# rx_board.net
KiCad netlist of a schematic drawn in EAGLE
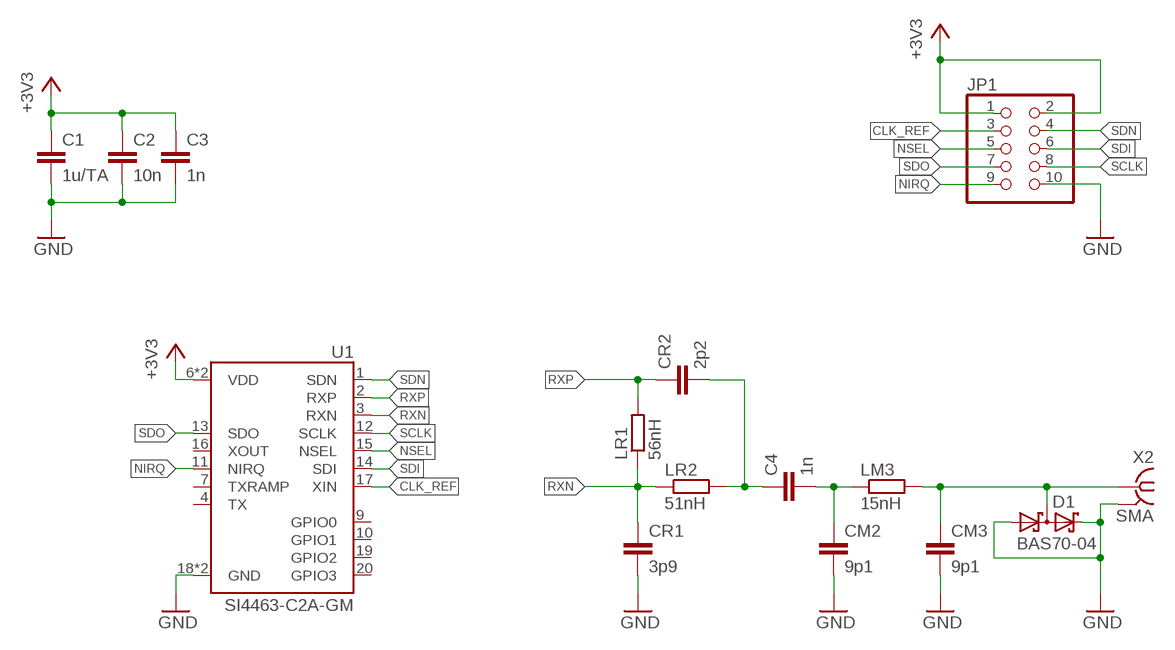
[diagram p0: schematic, sheet 1]

(export (version "E")
  (design (tool "Eeschema 10.0.6"))
  (components
    (comp (ref "C1")
      (value "1u/TA")
      (footprint "eagle-import:C1206")
      (libsource (lib "eagle-import") (part "C-EUC1206"))
    )
    (comp (ref "C2")
      (value "10n")
      (footprint "eagle-import:C0805")
      (libsource (lib "eagle-import") (part "C-EUC0805"))
    )
    (comp (ref "C3")
      (value "1n")
      (footprint "eagle-import:C0805")
      (libsource (lib "eagle-import") (part "C-EUC0805"))
    )
    (comp (ref "C4")
      (value "1n")
      (footprint "eagle-import:C0805")
      (libsource (lib "eagle-import") (part "C-EUC0805"))
    )
    (comp (ref "CM2")
      (value "9p1")
      (footprint "eagle-import:C0805")
      (libsource (lib "eagle-import") (part "C-EUC0805"))
    )
    (comp (ref "CM3")
      (value "9p1")
      (footprint "eagle-import:C0805")
      (libsource (lib "eagle-import") (part "C-EUC0805"))
    )
    (comp (ref "CR1")
      (value "3p9")
      (footprint "eagle-import:C0805")
      (libsource (lib "eagle-import") (part "C-EUC0805"))
    )
    (comp (ref "CR2")
      (value "2p2")
      (footprint "eagle-import:C0805")
      (libsource (lib "eagle-import") (part "C-EUC0805"))
    )
    (comp (ref "D1")
      (value "BAS70-04")
      (footprint "eagle-import:SOT23")
      (libsource (lib "eagle-import") (part "BAS70-04"))
    )
    (comp (ref "JP1")
      (value "PINHD-2X5/90")
      (footprint "eagle-import:2X05_90")
      (libsource (lib "eagle-import") (part "PINHD-2X5/90"))
    )
    (comp (ref "LM3")
      (value "15nH")
      (footprint "eagle-import:R0805")
      (libsource (lib "eagle-import") (part "R-EU_R0805"))
    )
    (comp (ref "LR1")
      (value "56nH")
      (footprint "eagle-import:R0805")
      (libsource (lib "eagle-import") (part "R-EU_R0805"))
    )
    (comp (ref "LR2")
      (value "51nH")
      (footprint "eagle-import:R0805")
      (libsource (lib "eagle-import") (part "R-EU_R0805"))
    )
    (comp (ref "U1")
      (value "SI4463-C2A-GM")
      (footprint "eagle-import:QFN50P400X400X90-20N")
      (fields (field (name "MF") "Silicon Labs"))
      (libsource (lib "eagle-import") (part "SI4463-C2A-GM"))
    )
    (comp (ref "X2")
      (value "SMA")
      (footprint "eagle-import:J502-ND-142-0701-871_876")
      (fields (field (name "MF") "JOHNSON COMPONENTS") (field (name "MPN") "142-0701-871"))
      (libsource (lib "eagle-import") (part "SMA-142-0701-871/876"))
    )
  )
  (nets
    (net (code "1") (name "+3V3") (class "Default")
      (node (ref "C1") (pin "1") (pinfunction "1_1") (pintype "passive"))
      (node (ref "C2") (pin "1") (pinfunction "1_1") (pintype "passive"))
      (node (ref "C3") (pin "1") (pinfunction "1_1") (pintype "passive"))
      (node (ref "JP1") (pin "1") (pinfunction "1_1") (pintype "passive"))
      (node (ref "JP1") (pin "2") (pinfunction "2_2") (pintype "passive"))
      (node (ref "U1") (pin "6") (pinfunction "VDD_6") (pintype "power_in"))
      (node (ref "U1") (pin "8") (pinfunction "VDD_8") (pintype "power_in"))
    )
    (net (code "2") (name "CLK_REF") (class "Default")
      (node (ref "JP1") (pin "3") (pinfunction "3_3") (pintype "passive"))
      (node (ref "U1") (pin "17") (pinfunction "XIN_17") (pintype "input"))
    )
    (net (code "3") (name "GND") (class "Default")
      (node (ref "C1") (pin "2") (pinfunction "2_2") (pintype "passive"))
      (node (ref "C2") (pin "2") (pinfunction "2_2") (pintype "passive"))
      (node (ref "C3") (pin "2") (pinfunction "2_2") (pintype "passive"))
      (node (ref "CM2") (pin "2") (pinfunction "2_2") (pintype "passive"))
      (node (ref "CM3") (pin "2") (pinfunction "2_2") (pintype "passive"))
      (node (ref "CR1") (pin "2") (pinfunction "2_2") (pintype "passive"))
      (node (ref "D1") (pin "1") (pinfunction "A1_1") (pintype "passive"))
      (node (ref "D1") (pin "2") (pinfunction "C2_2") (pintype "passive"))
      (node (ref "JP1") (pin "10") (pinfunction "10_10") (pintype "passive"))
      (node (ref "U1") (pin "18") (pinfunction "GND_18") (pintype "power_in"))
      (node (ref "U1") (pin "21") (pinfunction "GND_21") (pintype "power_in"))
      (node (ref "X2") (pin "G@1") (pinfunction "2_G@1") (pintype "passive"))
      (node (ref "X2") (pin "G@2") (pinfunction "2_G@2") (pintype "passive"))
      (node (ref "X2") (pin "G@3") (pinfunction "2_G@3") (pintype "passive"))
      (node (ref "X2") (pin "G@4") (pinfunction "2_G@4") (pintype "passive"))
    )
    (net (code "4") (name "NIRQ") (class "Default")
      (node (ref "JP1") (pin "9") (pinfunction "9_9") (pintype "passive"))
      (node (ref "U1") (pin "11") (pinfunction "NIRQ_11") (pintype "output"))
    )
    (net (code "5") (name "NSEL") (class "Default")
      (node (ref "JP1") (pin "5") (pinfunction "5_5") (pintype "passive"))
      (node (ref "U1") (pin "15") (pinfunction "NSEL_15") (pintype "input"))
    )
    (net (code "6") (name "Net-(C4-Pad1)") (class "Default")
      (node (ref "C4") (pin "1") (pinfunction "1_1") (pintype "passive"))
      (node (ref "CR2") (pin "2") (pinfunction "2_2") (pintype "passive"))
      (node (ref "LR2") (pin "2") (pinfunction "2_2") (pintype "passive"))
    )
    (net (code "7") (name "Net-(C4-Pad2)") (class "Default")
      (node (ref "C4") (pin "2") (pinfunction "2_2") (pintype "passive"))
      (node (ref "CM2") (pin "1") (pinfunction "1_1") (pintype "passive"))
      (node (ref "LM3") (pin "1") (pinfunction "1_1") (pintype "passive"))
    )
    (net (code "8") (name "Net-(D1-C1A2)") (class "Default")
      (node (ref "CM3") (pin "1") (pinfunction "1_1") (pintype "passive"))
      (node (ref "D1") (pin "3") (pinfunction "C1A2_3") (pintype "passive"))
      (node (ref "LM3") (pin "2") (pinfunction "2_2") (pintype "passive"))
      (node (ref "X2") (pin "1") (pinfunction "1_1") (pintype "passive"))
    )
    (net (code "9") (name "RXN") (class "Default")
      (node (ref "CR1") (pin "1") (pinfunction "1_1") (pintype "passive"))
      (node (ref "LR1") (pin "1") (pinfunction "1_1") (pintype "passive"))
      (node (ref "LR2") (pin "1") (pinfunction "1_1") (pintype "passive"))
      (node (ref "U1") (pin "3") (pinfunction "RXN_3") (pintype "input"))
    )
    (net (code "10") (name "RXP") (class "Default")
      (node (ref "CR2") (pin "1") (pinfunction "1_1") (pintype "passive"))
      (node (ref "LR1") (pin "2") (pinfunction "2_2") (pintype "passive"))
      (node (ref "U1") (pin "2") (pinfunction "RXP_2") (pintype "input"))
    )
    (net (code "11") (name "SCLK") (class "Default")
      (node (ref "JP1") (pin "8") (pinfunction "8_8") (pintype "passive"))
      (node (ref "U1") (pin "12") (pinfunction "SCLK_12") (pintype "input"))
    )
    (net (code "12") (name "SDI") (class "Default")
      (node (ref "JP1") (pin "6") (pinfunction "6_6") (pintype "passive"))
      (node (ref "U1") (pin "14") (pinfunction "SDI_14") (pintype "input"))
    )
    (net (code "13") (name "SDN") (class "Default")
      (node (ref "JP1") (pin "4") (pinfunction "4_4") (pintype "passive"))
      (node (ref "U1") (pin "1") (pinfunction "SDN_1") (pintype "input"))
    )
    (net (code "14") (name "SDO") (class "Default")
      (node (ref "JP1") (pin "7") (pinfunction "7_7") (pintype "passive"))
      (node (ref "U1") (pin "13") (pinfunction "SDO_13") (pintype "output"))
    )
    (net (code "15") (name "unconnected-(U1-GPIO0-Pad9)") (class "Default")
      (node (ref "U1") (pin "9") (pinfunction "GPIO0_9") (pintype "bidirectional"))
    )
    (net (code "16") (name "unconnected-(U1-GPIO1-Pad10)") (class "Default")
      (node (ref "U1") (pin "10") (pinfunction "GPIO1_10") (pintype "bidirectional"))
    )
    (net (code "17") (name "unconnected-(U1-GPIO2-Pad19)") (class "Default")
      (node (ref "U1") (pin "19") (pinfunction "GPIO2_19") (pintype "bidirectional"))
    )
    (net (code "18") (name "unconnected-(U1-GPIO3-Pad20)") (class "Default")
      (node (ref "U1") (pin "20") (pinfunction "GPIO3_20") (pintype "bidirectional"))
    )
    (net (code "19") (name "unconnected-(U1-TX-Pad4)") (class "Default")
      (node (ref "U1") (pin "4") (pinfunction "TX_4") (pintype "output"))
    )
    (net (code "20") (name "unconnected-(U1-TXRAMP-Pad7)") (class "Default")
      (node (ref "U1") (pin "7") (pinfunction "TXRAMP_7") (pintype "output"))
    )
    (net (code "21") (name "unconnected-(U1-XOUT-Pad16)") (class "Default")
      (node (ref "U1") (pin "16") (pinfunction "XOUT_16") (pintype "output"))
    )
  )
)
